# 3_Connectors.net
KiCad netlist of a schematic drawn in Altium Designer
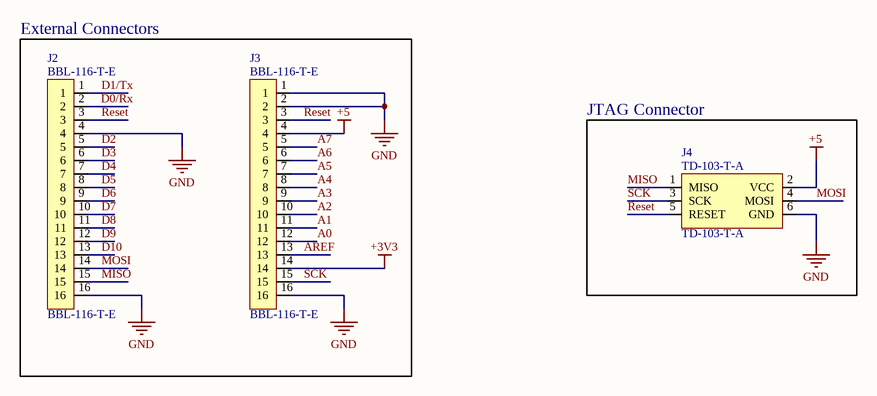
[diagram p0: 3_Connectors.SchDoc]

(export (version "E")
  (design (tool "Eeschema 10.0.6"))
  (components
    (comp (ref "J2")
      (value "BBL-116-T-E")
      (footprint "BBL-116-T-E")
      (description "16 POS Header, Through Hole")
      (libsource (lib "Generic Schematic lib") (part "BBL-116-T-E"))
    )
    (comp (ref "J3")
      (value "BBL-116-T-E")
      (footprint "BBL-116-T-E")
      (description "16 POS Header, Through Hole")
      (libsource (lib "Generic Schematic lib") (part "BBL-116-T-E"))
    )
    (comp (ref "J4")
      (value "TD-103-T-A")
      (footprint "TD-103-T-A")
      (description "AVRISP MK2")
      (libsource (lib "Generic Schematic lib") (part "TD-103-T-A"))
    )
  )
  (nets
    (net (code "1") (name "+3V3") (class "Default")
      (node (ref "J3") (pin "14") (pinfunction "14_14") (pintype "passive"))
    )
    (net (code "2") (name "+5") (class "Default")
      (node (ref "J3") (pin "4") (pinfunction "4_4") (pintype "passive"))
      (node (ref "J4") (pin "2") (pinfunction "VCC_2") (pintype "passive"))
    )
    (net (code "3") (name "/A0") (class "Default")
      (node (ref "J3") (pin "12") (pinfunction "12_12") (pintype "passive"))
    )
    (net (code "4") (name "/A1") (class "Default")
      (node (ref "J3") (pin "11") (pinfunction "11_11") (pintype "passive"))
    )
    (net (code "5") (name "/A2") (class "Default")
      (node (ref "J3") (pin "10") (pinfunction "10_10") (pintype "passive"))
    )
    (net (code "6") (name "/A3") (class "Default")
      (node (ref "J3") (pin "9") (pinfunction "9_9") (pintype "passive"))
    )
    (net (code "7") (name "/A4") (class "Default")
      (node (ref "J3") (pin "8") (pinfunction "8_8") (pintype "passive"))
    )
    (net (code "8") (name "/A5") (class "Default")
      (node (ref "J3") (pin "7") (pinfunction "7_7") (pintype "passive"))
    )
    (net (code "9") (name "/A6") (class "Default")
      (node (ref "J3") (pin "6") (pinfunction "6_6") (pintype "passive"))
    )
    (net (code "10") (name "/A7") (class "Default")
      (node (ref "J3") (pin "5") (pinfunction "5_5") (pintype "passive"))
    )
    (net (code "11") (name "/AREF") (class "Default")
      (node (ref "J3") (pin "13") (pinfunction "13_13") (pintype "passive"))
    )
    (net (code "12") (name "/D0{slash}Rx") (class "Default")
      (node (ref "J2") (pin "2") (pinfunction "2_2") (pintype "passive"))
    )
    (net (code "13") (name "/D1{slash}Tx") (class "Default")
      (node (ref "J2") (pin "1") (pinfunction "1_1") (pintype "passive"))
    )
    (net (code "14") (name "/D2") (class "Default")
      (node (ref "J2") (pin "5") (pinfunction "5_5") (pintype "passive"))
    )
    (net (code "15") (name "/D3") (class "Default")
      (node (ref "J2") (pin "6") (pinfunction "6_6") (pintype "passive"))
    )
    (net (code "16") (name "/D4") (class "Default")
      (node (ref "J2") (pin "7") (pinfunction "7_7") (pintype "passive"))
    )
    (net (code "17") (name "/D5") (class "Default")
      (node (ref "J2") (pin "8") (pinfunction "8_8") (pintype "passive"))
    )
    (net (code "18") (name "/D6") (class "Default")
      (node (ref "J2") (pin "9") (pinfunction "9_9") (pintype "passive"))
    )
    (net (code "19") (name "/D7") (class "Default")
      (node (ref "J2") (pin "10") (pinfunction "10_10") (pintype "passive"))
    )
    (net (code "20") (name "/D8") (class "Default")
      (node (ref "J2") (pin "11") (pinfunction "11_11") (pintype "passive"))
    )
    (net (code "21") (name "/D9") (class "Default")
      (node (ref "J2") (pin "12") (pinfunction "12_12") (pintype "passive"))
    )
    (net (code "22") (name "/D10") (class "Default")
      (node (ref "J2") (pin "13") (pinfunction "13_13") (pintype "passive"))
    )
    (net (code "23") (name "/MISO") (class "Default")
      (node (ref "J2") (pin "15") (pinfunction "15_15") (pintype "passive"))
      (node (ref "J4") (pin "1") (pinfunction "MISO_1") (pintype "passive"))
    )
    (net (code "24") (name "/MOSI") (class "Default")
      (node (ref "J2") (pin "14") (pinfunction "14_14") (pintype "passive"))
      (node (ref "J4") (pin "4") (pinfunction "MOSI_4") (pintype "passive"))
    )
    (net (code "25") (name "/Reset") (class "Default")
      (node (ref "J2") (pin "3") (pinfunction "3_3") (pintype "passive"))
      (node (ref "J3") (pin "3") (pinfunction "3_3") (pintype "passive"))
      (node (ref "J4") (pin "5") (pinfunction "RESET_5") (pintype "passive"))
    )
    (net (code "26") (name "/SCK") (class "Default")
      (node (ref "J3") (pin "15") (pinfunction "15_15") (pintype "passive"))
      (node (ref "J4") (pin "3") (pinfunction "SCK_3") (pintype "passive"))
    )
    (net (code "27") (name "GND") (class "Default")
      (node (ref "J2") (pin "16") (pinfunction "16_16") (pintype "passive"))
      (node (ref "J2") (pin "4") (pinfunction "4_4") (pintype "passive"))
      (node (ref "J3") (pin "1") (pinfunction "1_1") (pintype "passive"))
      (node (ref "J3") (pin "16") (pinfunction "16_16") (pintype "passive"))
      (node (ref "J3") (pin "2") (pinfunction "2_2") (pintype "passive"))
      (node (ref "J4") (pin "6") (pinfunction "GND_6") (pintype "passive"))
    )
  )
)
